# CPU.net
KiCad netlist of a schematic drawn in Altium Designer
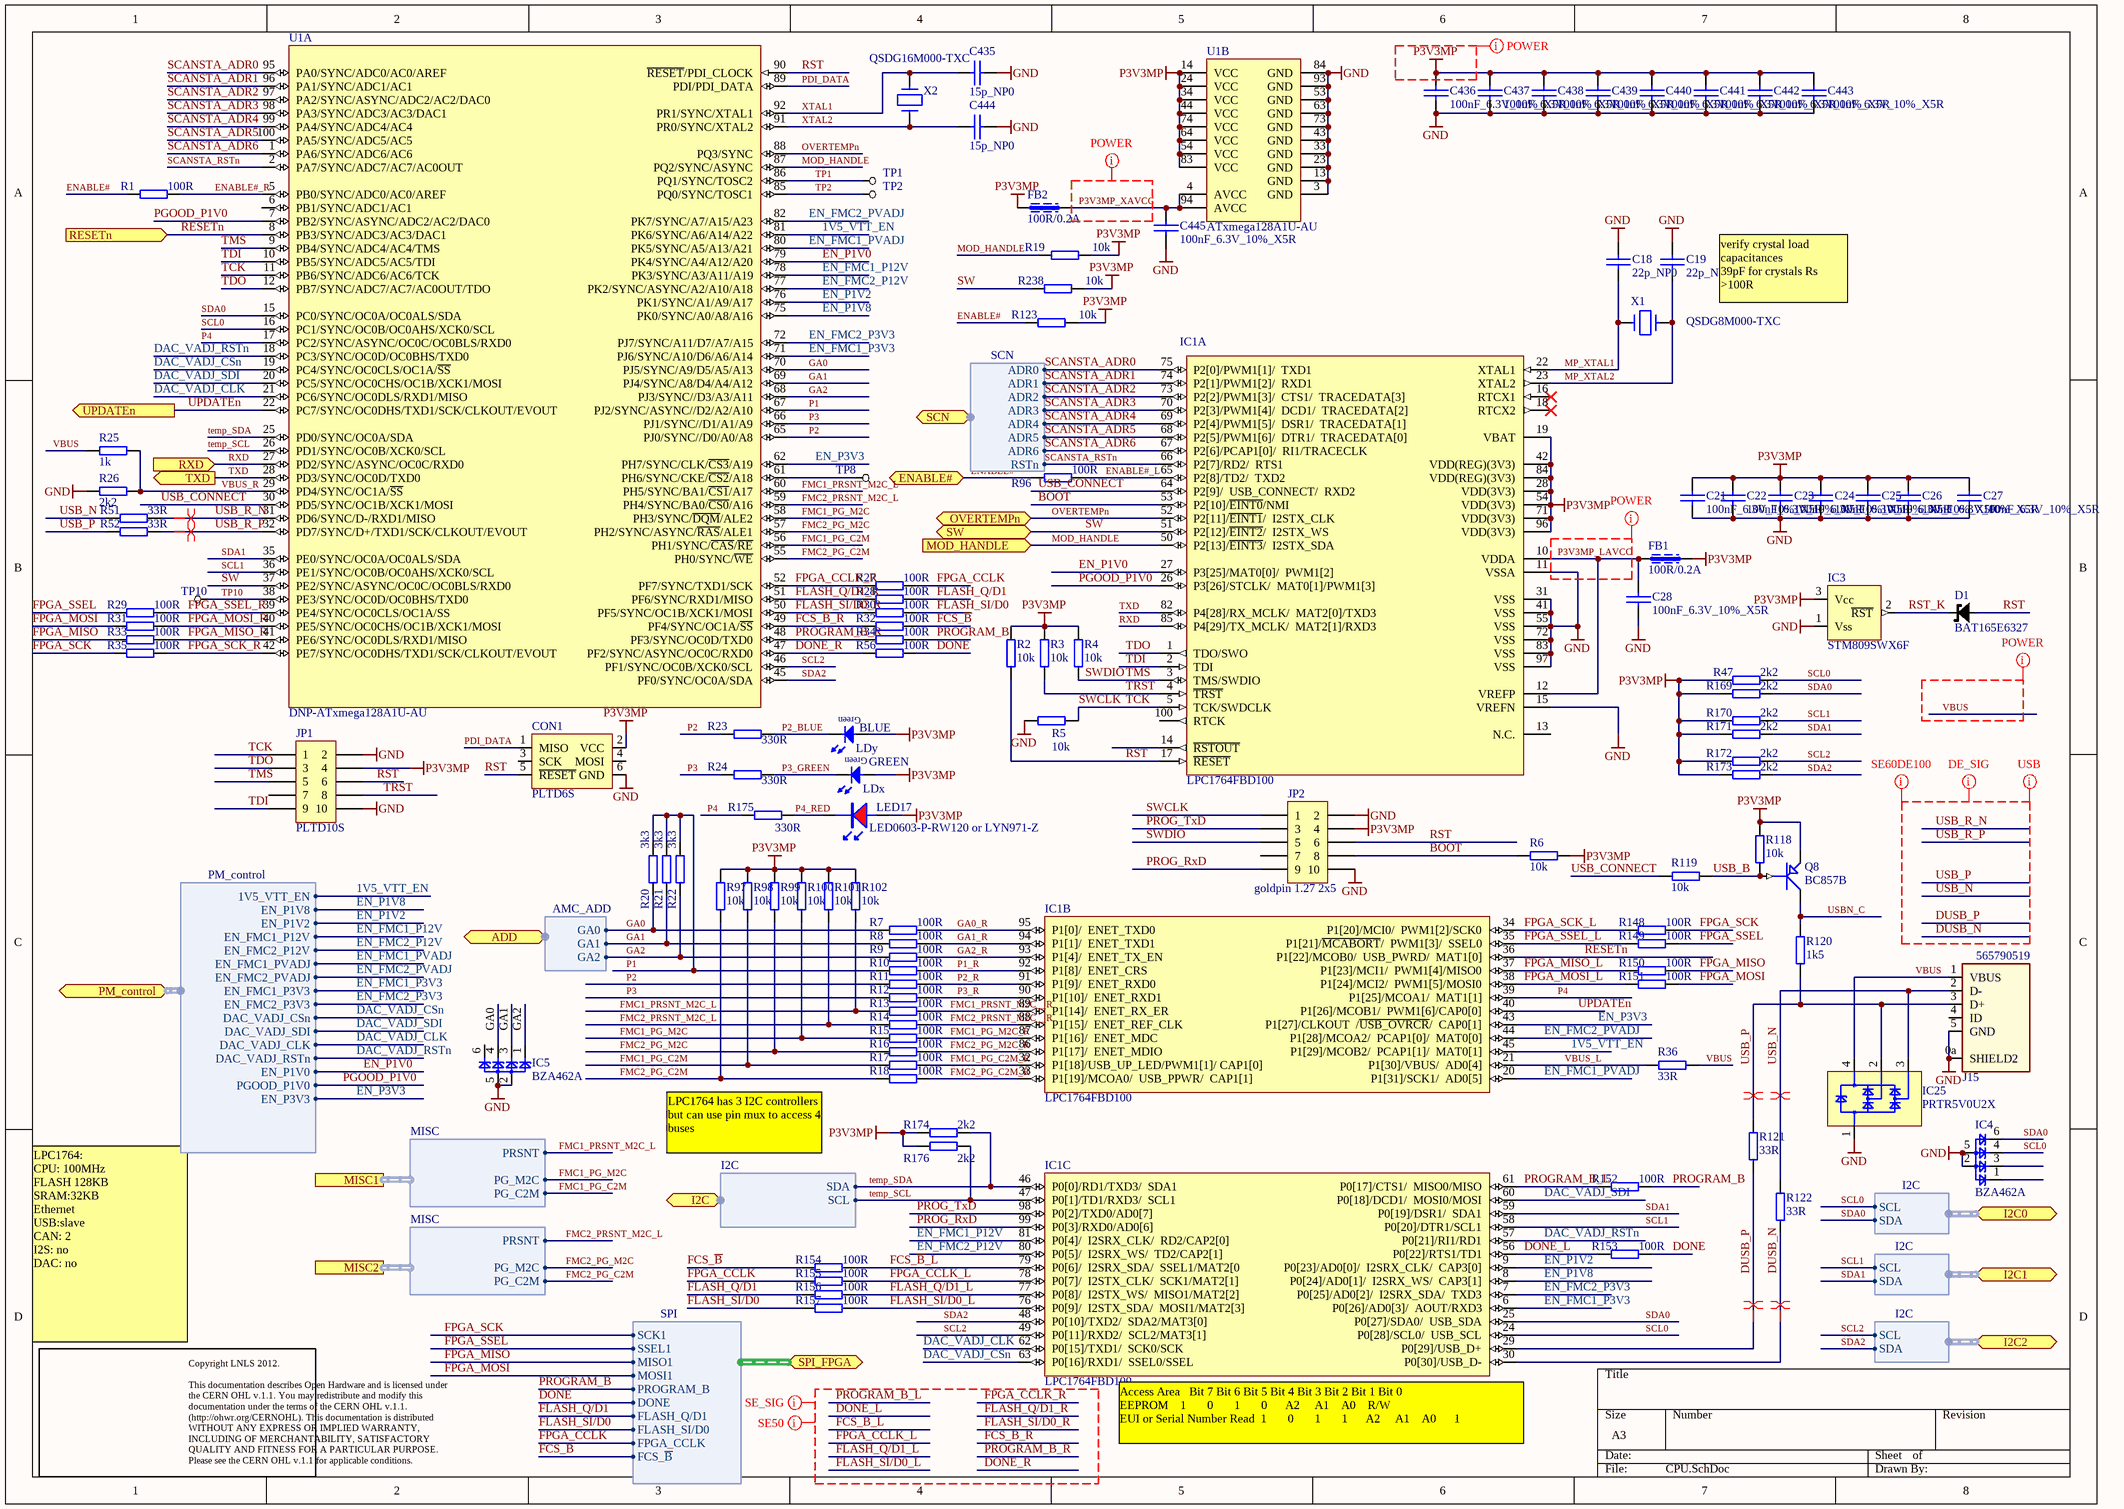
[diagram p0: CPU.SchDoc]

(export (version "E")
  (design (tool "Eeschema 10.0.6"))
  (components
    (comp (ref "C18")
      (value "22p_NP0")
      (footprint "0402C")
      (description "Capacitor SMD")
      (libsource (lib "LIBRARY_SCH") (part "CAP_SMD_0201"))
    )
    (comp (ref "C19")
      (value "22p_NP0")
      (footprint "0402C")
      (description "Capacitor SMD")
      (libsource (lib "LIBRARY_SCH") (part "CAP_SMD_0201"))
    )
    (comp (ref "C21")
      (value "100nF_6.3V_10%_X5R")
      (footprint "0201C")
      (description "Capacitor SMD")
      (libsource (lib "LIBRARY_SCH") (part "CAP_SMD_0201"))
    )
    (comp (ref "C22")
      (value "100nF_6.3V_10%_X5R")
      (footprint "0201C")
      (description "Capacitor SMD")
      (libsource (lib "LIBRARY_SCH") (part "CAP_SMD_0201"))
    )
    (comp (ref "C23")
      (value "100nF_6.3V_10%_X5R")
      (footprint "0201C")
      (description "Capacitor SMD")
      (libsource (lib "LIBRARY_SCH") (part "CAP_SMD_0201"))
    )
    (comp (ref "C24")
      (value "100nF_6.3V_10%_X5R")
      (footprint "0201C")
      (description "Capacitor SMD")
      (libsource (lib "LIBRARY_SCH") (part "CAP_SMD_0201"))
    )
    (comp (ref "C25")
      (value "100nF_6.3V_10%_X5R")
      (footprint "0201C")
      (description "Capacitor SMD")
      (libsource (lib "LIBRARY_SCH") (part "CAP_SMD_0201"))
    )
    (comp (ref "C26")
      (value "100nF_6.3V_10%_X5R")
      (footprint "0201C")
      (description "Capacitor SMD")
      (libsource (lib "LIBRARY_SCH") (part "CAP_SMD_0201"))
    )
    (comp (ref "C27")
      (value "100nF_6.3V_10%_X5R")
      (footprint "0201C")
      (description "Capacitor SMD")
      (libsource (lib "LIBRARY_SCH") (part "CAP_SMD_0201"))
    )
    (comp (ref "C28")
      (value "100nF_6.3V_10%_X5R")
      (footprint "0201C")
      (description "Capacitor SMD")
      (libsource (lib "LIBRARY_SCH") (part "CAP_SMD_0201"))
    )
    (comp (ref "C435")
      (value "15p_NP0")
      (footprint "0402C")
      (description "Capacitor SMD")
      (libsource (lib "LIBRARY_SCH") (part "CAP_SMD_0201"))
    )
    (comp (ref "C436")
      (value "100nF_6.3V_10%_X5R")
      (footprint "0201C")
      (description "Capacitor SMD")
      (libsource (lib "LIBRARY_SCH") (part "CAP_SMD_0201"))
    )
    (comp (ref "C437")
      (value "100nF_6.3V_10%_X5R")
      (footprint "0201C")
      (description "Capacitor SMD")
      (libsource (lib "LIBRARY_SCH") (part "CAP_SMD_0201"))
    )
    (comp (ref "C438")
      (value "100nF_6.3V_10%_X5R")
      (footprint "0201C")
      (description "Capacitor SMD")
      (libsource (lib "LIBRARY_SCH") (part "CAP_SMD_0201"))
    )
    (comp (ref "C439")
      (value "100nF_6.3V_10%_X5R")
      (footprint "0201C")
      (description "Capacitor SMD")
      (libsource (lib "LIBRARY_SCH") (part "CAP_SMD_0201"))
    )
    (comp (ref "C440")
      (value "100nF_6.3V_10%_X5R")
      (footprint "0201C")
      (description "Capacitor SMD")
      (libsource (lib "LIBRARY_SCH") (part "CAP_SMD_0201"))
    )
    (comp (ref "C441")
      (value "100nF_6.3V_10%_X5R")
      (footprint "0201C")
      (description "Capacitor SMD")
      (libsource (lib "LIBRARY_SCH") (part "CAP_SMD_0201"))
    )
    (comp (ref "C442")
      (value "100nF_6.3V_10%_X5R")
      (footprint "0201C")
      (description "Capacitor SMD")
      (libsource (lib "LIBRARY_SCH") (part "CAP_SMD_0201"))
    )
    (comp (ref "C443")
      (value "100nF_6.3V_10%_X5R")
      (footprint "0201C")
      (description "Capacitor SMD")
      (libsource (lib "LIBRARY_SCH") (part "CAP_SMD_0201"))
    )
    (comp (ref "C444")
      (value "15p_NP0")
      (footprint "0402C")
      (description "Capacitor SMD")
      (libsource (lib "LIBRARY_SCH") (part "CAP_SMD_0201"))
    )
    (comp (ref "C445")
      (value "100nF_6.3V_10%_X5R")
      (footprint "0201C")
      (description "Capacitor SMD")
      (libsource (lib "LIBRARY_SCH") (part "CAP_SMD_0201"))
    )
    (comp (ref "CON1")
      (value "PLTD6S")
      (footprint "PLTD6S")
      (description "6x 2.54mm SMT  dual row pin header")
      (libsource (lib "LIBRARY_SCH") (part "CON_ISP"))
    )
    (comp (ref "D1")
      (value "BAT165E6327")
      (footprint "SOD323")
      (description "500mA, 40V, Shottky Diode")
      (libsource (lib "LIBRARY_SCH") (part "D_BAT165"))
    )
    (comp (ref "FB1")
      (value "100R/0.2A")
      (footprint "0402L")
      (description "ferrite bead 100R@100MHz 0.2A")
      (libsource (lib "LIBRARY_SCH") (part "L_FERRITE_BEAD_0402"))
    )
    (comp (ref "FB2")
      (value "100R/0.2A")
      (footprint "0402L")
      (description "ferrite bead 100R@100MHz 0.2A")
      (libsource (lib "LIBRARY_SCH") (part "L_FERRITE_BEAD_0402"))
    )
    (comp (ref "IC1")
      (value "LPC1764FBD100")
      (footprint "LQFP100-LPC")
      (description "ARM Cortex-M3 procesor")
      (libsource (lib "LIBRARY_SCH") (part "UPC_LPC1764"))
    )
    (comp (ref "IC3")
      (value "STM809SWX6F")
      (footprint "SOT-23")
      (description "2.93V  Reset circuit")
      (libsource (lib "LIBRARY_SCH") (part "VMON_STM809"))
    )
    (comp (ref "IC4")
      (value "BZA462A")
      (footprint "SOT23-6")
      (description "Quadruple 4V ESD transient voltage suppressor")
      (libsource (lib "LIBRARY_SCH") (part "D_TVS_BZA462A"))
    )
    (comp (ref "IC5")
      (value "BZA462A")
      (footprint "SOT23-6")
      (description "Quadruple 4V ESD transient voltage suppressor")
      (libsource (lib "LIBRARY_SCH") (part "D_TVS_BZA462A"))
    )
    (comp (ref "IC25")
      (value "PRTR5V0U2X")
      (footprint "sot143b")
      (description "dual 5.5 ESD transient voltage suppressor")
      (libsource (lib "LIBRARY_SCH") (part "D_TVS_PRTR5V0U2X"))
    )
    (comp (ref "J15")
      (value "565790519")
      (footprint "CON_USB_565790519")
      (description "USB mini B connector (Molex)")
      (fields (field (name "PART NUMBER") "10133"))
      (libsource (lib "LIBRARY_SCH") (part "CON_USB_B_MINI_TH"))
    )
    (comp (ref "JP1")
      (value "PLTD10S")
      (footprint "PLTD10S")
      (description "Goldpin 2.54mm, male header")
      (libsource (lib "LIBRARY_SCH") (part "CON_2x5 2.54 male SMT"))
    )
    (comp (ref "JP2")
      (value "goldpin 1.27 2x5")
      (footprint "CON_2x5_MINI")
      (description "PBTD10S")
      (libsource (lib "sch") (part "CON_HEADER 5X2"))
    )
    (comp (ref "LDx")
      (value "GREEN")
      (footprint "LED_AVAGO_HSME-C120")
      (description "LED BLUE")
      (fields (field (name "AUTHOR") "CERN DEM JMW"))
      (libsource (lib "ICs And Semiconductors") (part "LED Green 1C 2A"))
    )
    (comp (ref "LDy")
      (value "BLUE")
      (footprint "LED_AVAGO_HSME-C120")
      (description "LED BLUE")
      (fields (field (name "AUTHOR") "CERN DEM JMW"))
      (libsource (lib "ICs And Semiconductors") (part "LED Green 1C 2A"))
    )
    (comp (ref "LED17")
      (value "LED0603-P-RW120 or LYN971-Z")
      (footprint "led_0603R")
      (description "LED 0603 red")
      (libsource (lib "LIBRARY_SCH") (part "LED_0603R"))
    )
    (comp (ref "Q8")
      (value "BC857B")
      (footprint "SOT-23")
      (description "Transistor")
      (libsource (lib "LIBRARY_SCH") (part "Q_BC857B"))
    )
    (comp (ref "R1")
      (value "100R")
      (footprint "0402R")
      (description "SMD Resistor")
      (libsource (lib "LIBRARY_SCH") (part "RES_0402"))
    )
    (comp (ref "R2")
      (value "10k")
      (footprint "0402R")
      (description "SMD Resistor")
      (libsource (lib "LIBRARY_SCH") (part "RES_0402"))
    )
    (comp (ref "R3")
      (value "10k")
      (footprint "0402R")
      (description "SMD Resistor")
      (libsource (lib "LIBRARY_SCH") (part "RES_0402"))
    )
    (comp (ref "R4")
      (value "10k")
      (footprint "0402R")
      (description "SMD Resistor")
      (libsource (lib "LIBRARY_SCH") (part "RES_0402"))
    )
    (comp (ref "R5")
      (value "10k")
      (footprint "0402R")
      (description "SMD Resistor")
      (libsource (lib "LIBRARY_SCH") (part "RES_0402"))
    )
    (comp (ref "R6")
      (value "10k")
      (footprint "0402R")
      (description "SMD Resistor")
      (libsource (lib "LIBRARY_SCH") (part "RES_0402"))
    )
    (comp (ref "R7")
      (value "100R")
      (footprint "0402R")
      (description "SMD Resistor")
      (libsource (lib "LIBRARY_SCH") (part "RES_0402"))
    )
    (comp (ref "R8")
      (value "100R")
      (footprint "0402R")
      (description "SMD Resistor")
      (libsource (lib "LIBRARY_SCH") (part "RES_0402"))
    )
    (comp (ref "R9")
      (value "100R")
      (footprint "0402R")
      (description "SMD Resistor")
      (libsource (lib "LIBRARY_SCH") (part "RES_0402"))
    )
    (comp (ref "R10")
      (value "100R")
      (footprint "0402R")
      (description "SMD Resistor")
      (libsource (lib "LIBRARY_SCH") (part "RES_0402"))
    )
    (comp (ref "R11")
      (value "100R")
      (footprint "0402R")
      (description "SMD Resistor")
      (libsource (lib "LIBRARY_SCH") (part "RES_0402"))
    )
    (comp (ref "R12")
      (value "100R")
      (footprint "0402R")
      (description "SMD Resistor")
      (libsource (lib "LIBRARY_SCH") (part "RES_0402"))
    )
    (comp (ref "R13")
      (value "100R")
      (footprint "0402R")
      (description "SMD Resistor")
      (libsource (lib "LIBRARY_SCH") (part "RES_0402"))
    )
    (comp (ref "R14")
      (value "100R")
      (footprint "0402R")
      (description "SMD Resistor")
      (libsource (lib "LIBRARY_SCH") (part "RES_0402"))
    )
    (comp (ref "R15")
      (value "100R")
      (footprint "0402R")
      (description "SMD Resistor")
      (libsource (lib "LIBRARY_SCH") (part "RES_0402"))
    )
    (comp (ref "R16")
      (value "100R")
      (footprint "0402R")
      (description "SMD Resistor")
      (libsource (lib "LIBRARY_SCH") (part "RES_0402"))
    )
    (comp (ref "R17")
      (value "100R")
      (footprint "0402R")
      (description "SMD Resistor")
      (libsource (lib "LIBRARY_SCH") (part "RES_0402"))
    )
    (comp (ref "R18")
      (value "100R")
      (footprint "0402R")
      (description "SMD Resistor")
      (libsource (lib "LIBRARY_SCH") (part "RES_0402"))
    )
    (comp (ref "R19")
      (value "10k")
      (footprint "0402R")
      (description "SMD Resistor")
      (libsource (lib "LIBRARY_SCH") (part "RES_0402"))
    )
    (comp (ref "R20")
      (value "3k3")
      (footprint "0402R")
      (description "SMD Resistor")
      (libsource (lib "LIBRARY_SCH") (part "RES_0402"))
    )
    (comp (ref "R21")
      (value "3k3")
      (footprint "0402R")
      (description "SMD Resistor")
      (libsource (lib "LIBRARY_SCH") (part "RES_0402"))
    )
    (comp (ref "R22")
      (value "3k3")
      (footprint "0402R")
      (description "SMD Resistor")
      (libsource (lib "LIBRARY_SCH") (part "RES_0402"))
    )
    (comp (ref "R23")
      (value "330R")
      (footprint "0402R")
      (description "SMD Resistor")
      (libsource (lib "LIBRARY_SCH") (part "RES_0402"))
    )
    (comp (ref "R24")
      (value "330R")
      (footprint "0402R")
      (description "SMD Resistor")
      (libsource (lib "LIBRARY_SCH") (part "RES_0402"))
    )
    (comp (ref "R25")
      (value "1k")
      (footprint "0402R")
      (description "SMD Resistor")
      (libsource (lib "LIBRARY_SCH") (part "RES_0402"))
    )
    (comp (ref "R26")
      (value "2k2")
      (footprint "0402R")
      (description "SMD Resistor")
      (libsource (lib "LIBRARY_SCH") (part "RES_0402"))
    )
    (comp (ref "R27")
      (value "100R")
      (footprint "0402R")
      (description "SMD Resistor")
      (libsource (lib "LIBRARY_SCH") (part "RES_0402"))
    )
    (comp (ref "R28")
      (value "100R")
      (footprint "0402R")
      (description "SMD Resistor")
      (libsource (lib "LIBRARY_SCH") (part "RES_0402"))
    )
    (comp (ref "R29")
      (value "100R")
      (footprint "0402R")
      (description "SMD Resistor")
      (libsource (lib "LIBRARY_SCH") (part "RES_0402"))
    )
    (comp (ref "R30")
      (value "100R")
      (footprint "0402R")
      (description "SMD Resistor")
      (libsource (lib "LIBRARY_SCH") (part "RES_0402"))
    )
    (comp (ref "R31")
      (value "100R")
      (footprint "0402R")
      (description "SMD Resistor")
      (libsource (lib "LIBRARY_SCH") (part "RES_0402"))
    )
    (comp (ref "R32")
      (value "100R")
      (footprint "0402R")
      (description "SMD Resistor")
      (libsource (lib "LIBRARY_SCH") (part "RES_0402"))
    )
    (comp (ref "R33")
      (value "100R")
      (footprint "0402R")
      (description "SMD Resistor")
      (libsource (lib "LIBRARY_SCH") (part "RES_0402"))
    )
    (comp (ref "R34")
      (value "100R")
      (footprint "0402R")
      (description "SMD Resistor")
      (libsource (lib "LIBRARY_SCH") (part "RES_0402"))
    )
    (comp (ref "R35")
      (value "100R")
      (footprint "0402R")
      (description "SMD Resistor")
      (libsource (lib "LIBRARY_SCH") (part "RES_0402"))
    )
    (comp (ref "R36")
      (value "33R")
      (footprint "0402R")
      (description "SMD Resistor")
      (libsource (lib "LIBRARY_SCH") (part "RES_0402"))
    )
    (comp (ref "R47")
      (value "2k2")
      (footprint "0402R")
      (description "SMD Resistor")
      (libsource (lib "LIBRARY_SCH") (part "RES_0402"))
    )
    (comp (ref "R51")
      (value "33R")
      (footprint "0402R")
      (description "SMD Resistor")
      (libsource (lib "LIBRARY_SCH") (part "RES_0402"))
    )
    (comp (ref "R52")
      (value "33R")
      (footprint "0402R")
      (description "SMD Resistor")
      (libsource (lib "LIBRARY_SCH") (part "RES_0402"))
    )
    (comp (ref "R56")
      (value "100R")
      (footprint "0402R")
      (description "SMD Resistor")
      (libsource (lib "LIBRARY_SCH") (part "RES_0402"))
    )
    (comp (ref "R96")
      (value "100R")
      (footprint "0402R")
      (description "SMD Resistor")
      (libsource (lib "LIBRARY_SCH") (part "RES_0402"))
    )
    (comp (ref "R97")
      (value "10k")
      (footprint "0402R")
      (description "SMD Resistor")
      (libsource (lib "LIBRARY_SCH") (part "RES_0402"))
    )
    (comp (ref "R98")
      (value "10k")
      (footprint "0402R")
      (description "SMD Resistor")
      (libsource (lib "LIBRARY_SCH") (part "RES_0402"))
    )
    (comp (ref "R99")
      (value "10k")
      (footprint "0402R")
      (description "SMD Resistor")
      (libsource (lib "LIBRARY_SCH") (part "RES_0402"))
    )
    (comp (ref "R100")
      (value "10k")
      (footprint "0402R")
      (description "SMD Resistor")
      (libsource (lib "LIBRARY_SCH") (part "RES_0402"))
    )
    (comp (ref "R101")
      (value "10k")
      (footprint "0402R")
      (description "SMD Resistor")
      (libsource (lib "LIBRARY_SCH") (part "RES_0402"))
    )
    (comp (ref "R102")
      (value "10k")
      (footprint "0402R")
      (description "SMD Resistor")
      (libsource (lib "LIBRARY_SCH") (part "RES_0402"))
    )
    (comp (ref "R118")
      (value "10k")
      (footprint "0402R")
      (description "SMD Resistor")
      (libsource (lib "LIBRARY_SCH") (part "RES_0402"))
    )
    (comp (ref "R119")
      (value "10k")
      (footprint "0402R")
      (description "SMD Resistor")
      (libsource (lib "LIBRARY_SCH") (part "RES_0402"))
    )
    (comp (ref "R120")
      (value "1k5")
      (footprint "0402R")
      (description "SMD Resistor")
      (libsource (lib "LIBRARY_SCH") (part "RES_0402"))
    )
    (comp (ref "R121")
      (value "33R")
      (footprint "0402R")
      (description "SMD Resistor")
      (libsource (lib "LIBRARY_SCH") (part "RES_0402"))
    )
    (comp (ref "R122")
      (value "33R")
      (footprint "0402R")
      (description "SMD Resistor")
      (libsource (lib "LIBRARY_SCH") (part "RES_0402"))
    )
    (comp (ref "R123")
      (value "10k")
      (footprint "0402R")
      (description "SMD Resistor")
      (libsource (lib "LIBRARY_SCH") (part "RES_0402"))
    )
    (comp (ref "R148")
      (value "100R")
      (footprint "0402R")
      (description "SMD Resistor")
      (libsource (lib "LIBRARY_SCH") (part "RES_0402"))
    )
    (comp (ref "R149")
      (value "100R")
      (footprint "0402R")
      (description "SMD Resistor")
      (libsource (lib "LIBRARY_SCH") (part "RES_0402"))
    )
    (comp (ref "R150")
      (value "100R")
      (footprint "0402R")
      (description "SMD Resistor")
      (libsource (lib "LIBRARY_SCH") (part "RES_0402"))
    )
    (comp (ref "R151")
      (value "100R")
      (footprint "0402R")
      (description "SMD Resistor")
      (libsource (lib "LIBRARY_SCH") (part "RES_0402"))
    )
    (comp (ref "R152")
      (value "100R")
      (footprint "0402R")
      (description "SMD Resistor")
      (libsource (lib "LIBRARY_SCH") (part "RES_0402"))
    )
    (comp (ref "R153")
      (value "100R")
      (footprint "0402R")
      (description "SMD Resistor")
      (libsource (lib "LIBRARY_SCH") (part "RES_0402"))
    )
    (comp (ref "R154")
      (value "100R")
      (footprint "0402R")
      (description "SMD Resistor")
      (libsource (lib "LIBRARY_SCH") (part "RES_0402"))
    )
    (comp (ref "R155")
      (value "100R")
      (footprint "0402R")
      (description "SMD Resistor")
      (libsource (lib "LIBRARY_SCH") (part "RES_0402"))
    )
    (comp (ref "R156")
      (value "100R")
      (footprint "0402R")
      (description "SMD Resistor")
      (libsource (lib "LIBRARY_SCH") (part "RES_0402"))
    )
    (comp (ref "R157")
      (value "100R")
      (footprint "0402R")
      (description "SMD Resistor")
      (libsource (lib "LIBRARY_SCH") (part "RES_0402"))
    )
    (comp (ref "R169")
      (value "2k2")
      (footprint "0402R")
      (description "SMD Resistor")
      (libsource (lib "LIBRARY_SCH") (part "RES_0402"))
    )
    (comp (ref "R170")
      (value "2k2")
      (footprint "0402R")
      (description "SMD Resistor")
      (libsource (lib "LIBRARY_SCH") (part "RES_0402"))
    )
    (comp (ref "R171")
      (value "2k2")
      (footprint "0402R")
      (description "SMD Resistor")
      (libsource (lib "LIBRARY_SCH") (part "RES_0402"))
    )
    (comp (ref "R172")
      (value "2k2")
      (footprint "0402R")
      (description "SMD Resistor")
      (libsource (lib "LIBRARY_SCH") (part "RES_0402"))
    )
    (comp (ref "R173")
      (value "2k2")
      (footprint "0402R")
      (description "SMD Resistor")
      (libsource (lib "LIBRARY_SCH") (part "RES_0402"))
    )
    (comp (ref "R174")
      (value "2k2")
      (footprint "0402R")
      (description "SMD Resistor")
      (libsource (lib "LIBRARY_SCH") (part "RES_0402"))
    )
    (comp (ref "R175")
      (value "330R")
      (footprint "0402R")
      (description "SMD Resistor")
      (libsource (lib "LIBRARY_SCH") (part "RES_0402"))
    )
    (comp (ref "R176")
      (value "2k2")
      (footprint "0402R")
      (description "SMD Resistor")
      (libsource (lib "LIBRARY_SCH") (part "RES_0402"))
    )
    (comp (ref "R238")
      (value "10k")
      (footprint "0402R")
      (description "SMD Resistor")
      (libsource (lib "LIBRARY_SCH") (part "RES_0402"))
    )
    (comp (ref "TP1")
      (value "TP")
      (footprint "TP")
      (description "Testpoint")
      (libsource (lib "LIBRARY_SCH") (part "TP"))
    )
    (comp (ref "TP2")
      (value "TP")
      (footprint "TP")
      (description "Testpoint")
      (libsource (lib "LIBRARY_SCH") (part "TP"))
    )
    (comp (ref "TP8")
      (value "TP")
      (footprint "TP")
      (description "Testpoint")
      (libsource (lib "LIBRARY_SCH") (part "TP"))
    )
    (comp (ref "TP10")
      (value "TP")
      (footprint "TP")
      (description "Testpoint")
      (libsource (lib "LIBRARY_SCH") (part "TP"))
    )
    (comp (ref "U1")
      (value "ATxmega128A1U-AU")
      (footprint "TQFP100")
      (fields (field (name "PUBLISHER") "Altium Limited"))
      (libsource (lib "LIBRARY_SCH") (part "UPC_ATxmega128A1-AU"))
    )
    (comp (ref "X1")
      (value "QSDG8M000-TXC")
      (footprint "XTAL_5.0*3.2")
      (description "miniature crystal oscillator (Maritex) QSDG8M000-TXC")
      (libsource (lib "LIBRARY_SCH") (part "X_CRYSTAL_SMD_5.0*3.2"))
    )
    (comp (ref "X2")
      (value "QSDG16M000-TXC")
      (footprint "XTAL_5.0*3.2")
      (description "miniature crystal oscillator (Maritex) QSDG8M000-TXC")
      (libsource (lib "LIBRARY_SCH") (part "X_CRYSTAL_SMD_5.0*3.2"))
    )
  )
  (nets
    (net (code "7") (name "/1V5_VTT_EN") (class "Default")
      (node (ref "IC1") (pin "45") (pinfunction "P1[29]/MCOB2/__PCAP1[1]/__MAT0[1]_45") (pintype "bidirectional"))
      (node (ref "U1") (pin "81") (pinfunction "PK6/SYNC/A6/A14/A22_81") (pintype "bidirectional"))
    )
    (net (code "8") (name "/BOOT") (class "Default")
      (node (ref "IC1") (pin "53") (pinfunction "P2[10]/~{EINT0}/NMI_53") (pintype "bidirectional"))
      (node (ref "JP2") (pin "8") (pinfunction "8_8") (pintype "passive"))
      (node (ref "R6") (pin "1") (pinfunction "1_1") (pintype "passive"))
    )
    (net (code "9") (name "/DAC_VADJ_CLK") (class "Default")
      (node (ref "IC1") (pin "62") (pinfunction "P0[15]/TXD1/__SCK0/SCK_62") (pintype "bidirectional"))
      (node (ref "U1") (pin "21") (pinfunction "PC6/SYNC/OC0DLS/RXD1/MISO_21") (pintype "bidirectional"))
    )
    (net (code "10") (name "/DAC_VADJ_CSn") (class "Default")
      (node (ref "IC1") (pin "63") (pinfunction "P0[16]/RXD1/__SSEL0/SSEL_63") (pintype "bidirectional"))
      (node (ref "U1") (pin "19") (pinfunction "PC4/SYNC/OC0CLS/OC1A/~{SS}_19") (pintype "bidirectional"))
    )
    (net (code "11") (name "/DAC_VADJ_RSTn") (class "Default")
      (node (ref "IC1") (pin "57") (pinfunction "P0[21]/RI1/RD1_57") (pintype "bidirectional"))
      (node (ref "U1") (pin "18") (pinfunction "PC3/SYNC/OC0D/OC0BHS/TXD0_18") (pintype "bidirectional"))
    )
    (net (code "12") (name "/DAC_VADJ_SDI") (class "Default")
      (node (ref "IC1") (pin "60") (pinfunction "P0[18]/DCD1/__MOSI0/MOSI_60") (pintype "bidirectional"))
      (node (ref "U1") (pin "20") (pinfunction "PC5/SYNC/OC0CHS/OC1B/XCK1/MOSI_20") (pintype "bidirectional"))
    )
    (net (code "13") (name "/DONE") (class "Default")
      (node (ref "R153") (pin "2") (pinfunction "2_2") (pintype "passive"))
      (node (ref "R56") (pin "2") (pinfunction "2_2") (pintype "passive"))
    )
    (net (code "14") (name "/DONE_L") (class "Default")
      (node (ref "IC1") (pin "56") (pinfunction "P0[22]/RTS1/TD1_56") (pintype "bidirectional"))
      (node (ref "R153") (pin "1") (pinfunction "1_1") (pintype "passive"))
    )
    (net (code "15") (name "/DONE_R") (class "Default")
      (node (ref "R56") (pin "1") (pinfunction "1_1") (pintype "passive"))
      (node (ref "U1") (pin "47") (pinfunction "PF2/SYNC/ASYNC/OC0C/RXD0_47") (pintype "bidirectional"))
    )
    (net (code "16") (name "/DUSB_N") (class "Default")
      (node (ref "IC1") (pin "30") (pinfunction "P0[30]/USB_D-_30") (pintype "bidirectional"))
      (node (ref "R122") (pin "1") (pinfunction "1_1") (pintype "passive"))
    )
    (net (code "17") (name "/DUSB_P") (class "Default")
      (node (ref "IC1") (pin "29") (pinfunction "P0[29]/USB_D+_29") (pintype "bidirectional"))
      (node (ref "R121") (pin "1") (pinfunction "1_1") (pintype "passive"))
    )
    (net (code "18") (name "/ENABLE#") (class "Default")
      (node (ref "R1") (pin "1") (pinfunction "1_1") (pintype "passive"))
      (node (ref "R123") (pin "1") (pinfunction "1_1") (pintype "passive"))
      (node (ref "R96") (pin "1") (pinfunction "1_1") (pintype "passive"))
    )
    (net (code "19") (name "/ENABLE#_L") (class "Default")
      (node (ref "IC1") (pin "65") (pinfunction "P2[8]/TD2/__TXD2_65") (pintype "bidirectional"))
      (node (ref "R96") (pin "2") (pinfunction "2_2") (pintype "passive"))
    )
    (net (code "20") (name "/ENABLE#_R") (class "Default")
      (node (ref "R1") (pin "2") (pinfunction "2_2") (pintype "passive"))
      (node (ref "U1") (pin "5") (pinfunction "PB0/SYNC/ADC0/AC0/AREF_5") (pintype "bidirectional"))
    )
    (net (code "21") (name "/EN_FMC1_P3V3") (class "Default")
      (node (ref "IC1") (pin "6") (pinfunction "P0[26]/AD0[3]/__AOUT/RXD3_6") (pintype "bidirectional"))
      (node (ref "U1") (pin "71") (pinfunction "PJ6/SYNC/A10/D6/A6/A14_71") (pintype "bidirectional"))
    )
    (net (code "22") (name "/EN_FMC1_P12V") (class "Default")
      (node (ref "IC1") (pin "81") (pinfunction "P0[4]/__I2SRX_CLK/__RD2/CAP2[0]_81") (pintype "bidirectional"))
      (node (ref "U1") (pin "78") (pinfunction "PK3/SYNC/A3/A11/A19_78") (pintype "bidirectional"))
    )
    (net (code "23") (name "/EN_FMC1_PVADJ") (class "Default")
      (node (ref "IC1") (pin "20") (pinfunction "P1[31]/SCK1/__AD0[5]_20") (pintype "bidirectional"))
      (node (ref "U1") (pin "80") (pinfunction "PK5/SYNC/A5/A13/A21_80") (pintype "bidirectional"))
    )
    (net (code "24") (name "/EN_FMC2_P3V3") (class "Default")
      (node (ref "IC1") (pin "7") (pinfunction "P0[25]/AD0[2]/__I2SRX_SDA/__TXD3_7") (pintype "bidirectional"))
      (node (ref "U1") (pin "72") (pinfunction "PJ7/SYNC/A11/D7/A7/A15_72") (pintype "bidirectional"))
    )
    (net (code "25") (name "/EN_FMC2_P12V") (class "Default")
      (node (ref "IC1") (pin "80") (pinfunction "P0[5]/__I2SRX_WS/__TD2/CAP2[1]_80") (pintype "bidirectional"))
      (node (ref "U1") (pin "77") (pinfunction "PK2/SYNC/ASYNC/A2/A10/A18_77") (pintype "bidirectional"))
    )
    (net (code "26") (name "/EN_FMC2_PVADJ") (class "Default")
      (node (ref "IC1") (pin "44") (pinfunction "P1[28]/MCOA2/__PCAP1[0]/__MAT0[0]_44") (pintype "bidirectional"))
      (node (ref "U1") (pin "82") (pinfunction "PK7/SYNC/A7/A15/A23_82") (pintype "bidirectional"))
    )
    (net (code "27") (name "/EN_P1V0") (class "Default")
      (node (ref "IC1") (pin "27") (pinfunction "P3[25]/MAT0[0]/__PWM1[2]_27") (pintype "bidirectional"))
      (node (ref "U1") (pin "79") (pinfunction "PK4/SYNC/A4/A12/A20_79") (pintype "bidirectional"))
    )
    (net (code "28") (name "/EN_P1V2") (class "Default")
      (node (ref "IC1") (pin "9") (pinfunction "P0[23]/AD0[0]/__I2SRX_CLK/__CAP3[0]_9") (pintype "bidirectional"))
      (node (ref "U1") (pin "76") (pinfunction "PK1/SYNC/A1/A9/A17_76") (pintype "bidirectional"))
    )
    (net (code "29") (name "/EN_P1V8") (class "Default")
      (node (ref "IC1") (pin "8") (pinfunction "P0[24]/AD0[1]/__I2SRX_WS/__CAP3[1]_8") (pintype "bidirectional"))
      (node (ref "U1") (pin "75") (pinfunction "PK0/SYNC/A0/A8/A16_75") (pintype "bidirectional"))
    )
    (net (code "30") (name "/EN_P3V3") (class "Default")
      (node (ref "IC1") (pin "43") (pinfunction "P1[27]/CLKOUT__/~{USB_OVRCR}/__CAP0[1]_43") (pintype "bidirectional"))
      (node (ref "U1") (pin "62") (pinfunction "PH7/SYNC/CLK/~{CS3}/A19_62") (pintype "bidirectional"))
    )
    (net (code "31") (name "/FCS_~{B}") (class "Default")
      (node (ref "R154") (pin "1") (pinfunction "1_1") (pintype "passive"))
      (node (ref "R32") (pin "2") (pinfunction "2_2") (pintype "passive"))
    )
    (net (code "32") (name "/FCS_~{B}_L") (class "Default")
      (node (ref "IC1") (pin "79") (pinfunction "P0[6]/__I2SRX_SDA/__SSEL1/MAT2[0_79") (pintype "bidirectional"))
      (node (ref "R154") (pin "2") (pinfunction "2_2") (pintype "passive"))
    )
    (net (code "33") (name "/FCS_~{B}_R") (class "Default")
      (node (ref "R32") (pin "1") (pinfunction "1_1") (pintype "passive"))
      (node (ref "U1") (pin "49") (pinfunction "PF4/SYNC/OC1A/~{SS}_49") (pintype "bidirectional"))
    )
    (net (code "34") (name "/FLASH_Q{slash}D1") (class "Default")
      (node (ref "R156") (pin "1") (pinfunction "1_1") (pintype "passive"))
      (node (ref "R28") (pin "2") (pinfunction "2_2") (pintype "passive"))
    )
    (net (code "35") (name "/FLASH_Q{slash}D1_L") (class "Default")
      (node (ref "IC1") (pin "77") (pinfunction "P0[8]/__I2STX_WS/__MISO1/MAT2[2]_77") (pintype "bidirectional"))
      (node (ref "R156") (pin "2") (pinfunction "2_2") (pintype "passive"))
    )
    (net (code "36") (name "/FLASH_Q{slash}D1_R") (class "Default")
      (node (ref "R28") (pin "1") (pinfunction "1_1") (pintype "passive"))
      (node (ref "U1") (pin "51") (pinfunction "PF6/SYNC/RXD1/MISO_51") (pintype "bidirectional"))
    )
    (net (code "37") (name "/FLASH_SI{slash}D0") (class "Default")
      (node (ref "R157") (pin "1") (pinfunction "1_1") (pintype "passive"))
      (node (ref "R30") (pin "2") (pinfunction "2_2") (pintype "passive"))
    )
    (net (code "38") (name "/FLASH_SI{slash}D0_L") (class "Default")
      (node (ref "IC1") (pin "76") (pinfunction "P0[9]/__I2STX_SDA/__MOSI1/MAT2[3]_76") (pintype "bidirectional"))
      (node (ref "R157") (pin "2") (pinfunction "2_2") (pintype "passive"))
    )
    (net (code "39") (name "/FLASH_SI{slash}D0_R") (class "Default")
      (node (ref "R30") (pin "1") (pinfunction "1_1") (pintype "passive"))
      (node (ref "U1") (pin "50") (pinfunction "PF5/SYNC/OC1B/XCK1/MOSI_50") (pintype "bidirectional"))
    )
    (net (code "40") (name "/FMC1_PG_C2M") (class "Default")
      (node (ref "R17") (pin "1") (pinfunction "1_1") (pintype "passive"))
      (node (ref "R98") (pin "1") (pinfunction "1_1") (pintype "passive"))
      (node (ref "U1") (pin "56") (pinfunction "PH1/SYNC/~{CAS}/~{RE}_56") (pintype "bidirectional"))
    )
    (net (code "41") (name "/FMC1_PG_C2M_R") (class "Default")
      (node (ref "IC1") (pin "32") (pinfunction "P1[18]/USB_UP_LED/PWM1[1]/_CAP1[0]_32") (pintype "bidirectional"))
      (node (ref "R17") (pin "2") (pinfunction "2_2") (pintype "passive"))
    )
    (net (code "42") (name "/FMC1_PG_M2C") (class "Default")
      (node (ref "R100") (pin "1") (pinfunction "1_1") (pintype "passive"))
      (node (ref "R15") (pin "1") (pinfunction "1_1") (pintype "passive"))
      (node (ref "U1") (pin "58") (pinfunction "PH3/SYNC/~{DQM}/ALE2_58") (pintype "bidirectional"))
    )
    (net (code "43") (name "/FMC1_PG_M2C_R") (class "Default")
      (node (ref "IC1") (pin "87") (pinfunction "P1[16]/__ENET_MDC_87") (pintype "bidirectional"))
      (node (ref "R15") (pin "2") (pinfunction "2_2") (pintype "passive"))
    )
    (net (code "44") (name "/FMC1_PRSNT_M2C_L") (class "Default")
      (node (ref "R102") (pin "1") (pinfunction "1_1") (pintype "passive"))
      (node (ref "R13") (pin "1") (pinfunction "1_1") (pintype "passive"))
      (node (ref "U1") (pin "60") (pinfunction "PH5/SYNC/BA1/~{CS1}/A17_60") (pintype "bidirectional"))
    )
    (net (code "45") (name "/FMC1_PRSNT_M2C__R") (class "Default")
      (node (ref "IC1") (pin "89") (pinfunction "P1[14]/__ENET_RX_ER_89") (pintype "bidirectional"))
      (node (ref "R13") (pin "2") (pinfunction "2_2") (pintype "passive"))
    )
    (net (code "46") (name "/FMC2_PG_C2M") (class "Default")
      (node (ref "R18") (pin "1") (pinfunction "1_1") (pintype "passive"))
      (node (ref "R97") (pin "1") (pinfunction "1_1") (pintype "passive"))
      (node (ref "U1") (pin "55") (pinfunction "PH0/SYNC/~{WE}_55") (pintype "bidirectional"))
    )
    (net (code "47") (name "/FMC2_PG_C2M_R") (class "Default")
      (node (ref "IC1") (pin "33") (pinfunction "P1[19]/MCOA0/__USB_PPWR/__CAP1[1]_33") (pintype "bidirectional"))
      (node (ref "R18") (pin "2") (pinfunction "2_2") (pintype "passive"))
    )
    (net (code "48") (name "/FMC2_PG_M2C") (class "Default")
      (node (ref "R16") (pin "1") (pinfunction "1_1") (pintype "passive"))
      (node (ref "R99") (pin "1") (pinfunction "1_1") (pintype "passive"))
      (node (ref "U1") (pin "57") (pinfunction "PH2/SYNC/ASYNC/~{RAS}/ALE1_57") (pintype "bidirectional"))
    )
    (net (code "49") (name "/FMC2_PG_M2C_R") (class "Default")
      (node (ref "IC1") (pin "86") (pinfunction "P1[17]/__ENET_MDIO_86") (pintype "bidirectional"))
      (node (ref "R16") (pin "2") (pinfunction "2_2") (pintype "passive"))
    )
    (net (code "50") (name "/FMC2_PRSNT_M2C_L") (class "Default")
      (node (ref "R101") (pin "1") (pinfunction "1_1") (pintype "passive"))
      (node (ref "R14") (pin "1") (pinfunction "1_1") (pintype "passive"))
      (node (ref "U1") (pin "59") (pinfunction "PH4/SYNC/BA0/~{CS0}/A16_59") (pintype "bidirectional"))
    )
    (net (code "51") (name "/FMC2_PRSNT_M2C__R") (class "Default")
      (node (ref "IC1") (pin "88") (pinfunction "P1[15]/__ENET_REF_CLK_88") (pintype "bidirectional"))
      (node (ref "R14") (pin "2") (pinfunction "2_2") (pintype "passive"))
    )
    (net (code "52") (name "/FPGA_CCLK") (class "Default")
      (node (ref "R155") (pin "1") (pinfunction "1_1") (pintype "passive"))
      (node (ref "R27") (pin "2") (pinfunction "2_2") (pintype "passive"))
    )
    (net (code "53") (name "/FPGA_CCLK_L") (class "Default")
      (node (ref "IC1") (pin "78") (pinfunction "P0[7]/__I2STX_CLK/__SCK1/MAT2[1]_78") (pintype "bidirectional"))
      (node (ref "R155") (pin "2") (pinfunction "2_2") (pintype "passive"))
    )
    (net (code "54") (name "/FPGA_CCLK_R") (class "Default")
      (node (ref "R27") (pin "1") (pinfunction "1_1") (pintype "passive"))
      (node (ref "U1") (pin "52") (pinfunction "PF7/SYNC/TXD1/SCK_52") (pintype "bidirectional"))
    )
    (net (code "55") (name "/FPGA_MISO") (class "Default")
      (node (ref "R150") (pin "2") (pinfunction "2_2") (pintype "passive"))
      (node (ref "R33") (pin "1") (pinfunction "1_1") (pintype "passive"))
    )
    (net (code "56") (name "/FPGA_MISO_L") (class "Default")
      (node (ref "IC1") (pin "37") (pinfunction "P1[23]/MCI1/__PWM1[4]/MISO0_37") (pintype "bidirectional"))
      (node (ref "R150") (pin "1") (pinfunction "1_1") (pintype "passive"))
    )
    (net (code "57") (name "/FPGA_MISO_R") (class "Default")
      (node (ref "R33") (pin "2") (pinfunction "2_2") (pintype "passive"))
      (node (ref "U1") (pin "41") (pinfunction "PE6/SYNC/OC0DLS/RXD1/MISO_41") (pintype "bidirectional"))
    )
    (net (code "58") (name "/FPGA_MOSI") (class "Default")
      (node (ref "R151") (pin "2") (pinfunction "2_2") (pintype "passive"))
      (node (ref "R31") (pin "1") (pinfunction "1_1") (pintype "passive"))
    )
    (net (code "59") (name "/FPGA_MOSI_L") (class "Default")
      (node (ref "IC1") (pin "38") (pinfunction "P1[24]/MCI2/__PWM1[5]/MOSI0_38") (pintype "bidirectional"))
      (node (ref "R151") (pin "1") (pinfunction "1_1") (pintype "passive"))
    )
    (net (code "60") (name "/FPGA_MOSI_R") (class "Default")
      (node (ref "R31") (pin "2") (pinfunction "2_2") (pintype "passive"))
      (node (ref "U1") (pin "40") (pinfunction "PE5/SYNC/OC0CHS/OC1B/XCK1/MOSI_40") (pintype "bidirectional"))
    )
    (net (code "61") (name "/FPGA_SCK") (class "Default")
      (node (ref "R148") (pin "2") (pinfunction "2_2") (pintype "passive"))
      (node (ref "R35") (pin "1") (pinfunction "1_1") (pintype "passive"))
    )
    (net (code "62") (name "/FPGA_SCK_L") (class "Default")
      (node (ref "IC1") (pin "34") (pinfunction "P1[20]/MCI0/__PWM1[2]/SCK0_34") (pintype "bidirectional"))
      (node (ref "R148") (pin "1") (pinfunction "1_1") (pintype "passive"))
    )
    (net (code "63") (name "/FPGA_SCK_R") (class "Default")
      (node (ref "R35") (pin "2") (pinfunction "2_2") (pintype "passive"))
      (node (ref "U1") (pin "42") (pinfunction "PE7/SYNC/OC0DHS/TXD1/SCK/CLKOUT/EVOUT_42") (pintype "bidirectional"))
    )
    (net (code "64") (name "/FPGA_SSEL") (class "Default")
      (node (ref "R149") (pin "2") (pinfunction "2_2") (pintype "passive"))
      (node (ref "R29") (pin "1") (pinfunction "1_1") (pintype "passive"))
    )
    (net (code "65") (name "/FPGA_SSEL_L") (class "Default")
      (node (ref "IC1") (pin "35") (pinfunction "P1[21]/~{MCABORT}/__PWM1[3]/__SSEL0_35") (pintype "bidirectional"))
      (node (ref "R149") (pin "1") (pinfunction "1_1") (pintype "passive"))
    )
    (net (code "66") (name "/FPGA_SSEL_R") (class "Default")
      (node (ref "R29") (pin "2") (pinfunction "2_2") (pintype "passive"))
      (node (ref "U1") (pin "39") (pinfunction "PE4/SYNC/OC0CLS/OC1A/SS_39") (pintype "bidirectional"))
    )
    (net (code "67") (name "/GA0") (class "Default")
      (node (ref "IC5") (pin "4") (pinfunction "4_4") (pintype "passive"))
      (node (ref "R20") (pin "1") (pinfunction "1_1") (pintype "passive"))
      (node (ref "R7") (pin "1") (pinfunction "1_1") (pintype "passive"))
      (node (ref "U1") (pin "70") (pinfunction "PJ5/SYNC/A9/D5/A5/A13_70") (pintype "bidirectional"))
    )
    (net (code "68") (name "/GA0_R") (class "Default")
      (node (ref "IC1") (pin "95") (pinfunction "P1[0]/__ENET_TXD0_95") (pintype "bidirectional"))
      (node (ref "R7") (pin "2") (pinfunction "2_2") (pintype "passive"))
    )
    (net (code "69") (name "/GA1") (class "Default")
      (node (ref "IC5") (pin "3") (pinfunction "3_3") (pintype "passive"))
      (node (ref "R21") (pin "1") (pinfunction "1_1") (pintype "passive"))
      (node (ref "R8") (pin "1") (pinfunction "1_1") (pintype "passive"))
      (node (ref "U1") (pin "69") (pinfunction "PJ4/SYNC/A8/D4/A4/A12_69") (pintype "bidirectional"))
    )
    (net (code "70") (name "/GA1_R") (class "Default")
      (node (ref "IC1") (pin "94") (pinfunction "P1[1]/__ENET_TXD1_94") (pintype "bidirectional"))
      (node (ref "R8") (pin "2") (pinfunction "2_2") (pintype "passive"))
    )
    (net (code "71") (name "/GA2") (class "Default")
      (node (ref "IC5") (pin "1") (pinfunction "1_1") (pintype "passive"))
      (node (ref "R22") (pin "1") (pinfunction "1_1") (pintype "passive"))
      (node (ref "R9") (pin "1") (pinfunction "1_1") (pintype "passive"))
      (node (ref "U1") (pin "68") (pinfunction "PJ3/SYNC//D3/A3/A11_68") (pintype "bidirectional"))
    )
    (net (code "72") (name "/GA2_R") (class "Default")
      (node (ref "IC1") (pin "93") (pinfunction "P1[4]/__ENET_TX_EN_93") (pintype "bidirectional"))
      (node (ref "R9") (pin "2") (pinfunction "2_2") (pintype "passive"))
    )
    (net (code "73") (name "/MOD_HANDLE") (class "Default")
      (node (ref "IC1") (pin "50") (pinfunction "P2[13]/~{EINT3}/__I2STX_SDA_50") (pintype "bidirectional"))
      (node (ref "R19") (pin "1") (pinfunction "1_1") (pintype "passive"))
      (node (ref "U1") (pin "87") (pinfunction "PQ2/SYNC/ASYNC_87") (pintype "bidirectional"))
    )
    (net (code "74") (name "/MP_XTAL1") (class "Default")
      (node (ref "C18") (pin "2") (pinfunction "2_2") (pintype "passive"))
      (node (ref "IC1") (pin "22") (pinfunction "XTAL1_22") (pintype "input"))
      (node (ref "X1") (pin "1") (pinfunction "1_1") (pintype "passive"))
    )
    (net (code "75") (name "/MP_XTAL2") (class "Default")
      (node (ref "C19") (pin "2") (pinfunction "2_2") (pintype "passive"))
      (node (ref "IC1") (pin "23") (pinfunction "XTAL2_23") (pintype "output"))
      (node (ref "X1") (pin "2") (pinfunction "2_2") (pintype "passive"))
    )
    (net (code "76") (name "/OVERTEMPn") (class "Default")
      (node (ref "IC1") (pin "52") (pinfunction "P2[11]/~{EINT1}/__I2STX_CLK_52") (pintype "bidirectional"))
      (node (ref "U1") (pin "88") (pinfunction "PQ3/SYNC_88") (pintype "bidirectional"))
    )
    (net (code "77") (name "/P1") (class "Default")
      (node (ref "R10") (pin "1") (pinfunction "1_1") (pintype "passive"))
      (node (ref "R20") (pin "2") (pinfunction "2_2") (pintype "passive"))
      (node (ref "R21") (pin "2") (pinfunction "2_2") (pintype "passive"))
      (node (ref "R22") (pin "2") (pinfunction "2_2") (pintype "passive"))
      (node (ref "U1") (pin "67") (pinfunction "PJ2/SYNC/ASYNC//D2/A2/A10_67") (pintype "bidirectional"))
    )
    (net (code "78") (name "/P1_R") (class "Default")
      (node (ref "IC1") (pin "92") (pinfunction "P1[8]/__ENET_CRS_92") (pintype "bidirectional"))
      (node (ref "R10") (pin "2") (pinfunction "2_2") (pintype "passive"))
    )
    (net (code "79") (name "/P2") (class "Default")
      (node (ref "R11") (pin "1") (pinfunction "1_1") (pintype "passive"))
      (node (ref "R23") (pin "1") (pinfunction "1_1") (pintype "passive"))
      (node (ref "U1") (pin "65") (pinfunction "PJ0/SYNC//D0/A0/A8_65") (pintype "bidirectional"))
    )
    (net (code "80") (name "/P2_BLUE") (class "Default")
      (node (ref "LDy") (pin "1") (pinfunction "C_1") (pintype "passive"))
      (node (ref "R23") (pin "2") (pinfunction "2_2") (pintype "passive"))
    )
    (net (code "81") (name "/P2_R") (class "Default")
      (node (ref "IC1") (pin "91") (pinfunction "P1[9]/__ENET_RXD0_91") (pintype "bidirectional"))
      (node (ref "R11") (pin "2") (pinfunction "2_2") (pintype "passive"))
    )
    (net (code "82") (name "/P3") (class "Default")
      (node (ref "R12") (pin "1") (pinfunction "1_1") (pintype "passive"))
      (node (ref "R24") (pin "1") (pinfunction "1_1") (pintype "passive"))
      (node (ref "U1") (pin "66") (pinfunction "PJ1/SYNC//D1/A1/A9_66") (pintype "bidirectional"))
    )
    (net (code "83") (name "/P3V3MP_LAVCC") (class "Default")
      (node (ref "C28") (pin "1") (pinfunction "1_1") (pintype "passive"))
      (node (ref "FB1") (pin "1") (pinfunction "1_1") (pintype "passive"))
      (node (ref "IC1") (pin "10") (pinfunction "VDDA_10") (pintype "power_in"))
      (node (ref "IC1") (pin "12") (pinfunction "VREFP_12") (pintype "power_in"))
    )
    (net (code "84") (name "/P3V3MP_XAVCC") (class "Default")
      (node (ref "C445") (pin "1") (pinfunction "1_1") (pintype "passive"))
      (node (ref "FB2") (pin "2") (pinfunction "2_2") (pintype "passive"))
      (node (ref "U1") (pin "4") (pinfunction "AVCC_4") (pintype "power_in"))
      (node (ref "U1") (pin "94") (pinfunction "AVCC_94") (pintype "power_in"))
    )
    (net (code "85") (name "/P3_GREEN") (class "Default")
      (node (ref "LDx") (pin "1") (pinfunction "C_1") (pintype "passive"))
      (node (ref "R24") (pin "2") (pinfunction "2_2") (pintype "passive"))
    )
    (net (code "86") (name "/P3_R") (class "Default")
      (node (ref "IC1") (pin "90") (pinfunction "P1[10]/__ENET_RXD1_90") (pintype "bidirectional"))
      (node (ref "R12") (pin "2") (pinfunction "2_2") (pintype "passive"))
    )
    (net (code "87") (name "/P4") (class "Default")
      (node (ref "IC1") (pin "39") (pinfunction "P1[25]/MCOA1/__MAT1[1]_39") (pintype "bidirectional"))
      (node (ref "R175") (pin "1") (pinfunction "1_1") (pintype "passive"))
      (node (ref "U1") (pin "17") (pinfunction "PC2/SYNC/ASYNC/OC0C/OC0BLS/RXD0_17") (pintype "bidirectional"))
    )
    (net (code "88") (name "/P4_RED") (class "Default")
      (node (ref "LED17") (pin "K") (pinfunction "K_K") (pintype "passive"))
      (node (ref "R175") (pin "2") (pinfunction "2_2") (pintype "passive"))
    )
    (net (code "89") (name "/PDI_DATA") (class "Default")
      (node (ref "CON1") (pin "1") (pinfunction "MISO_1") (pintype "passive"))
      (node (ref "U1") (pin "89") (pinfunction "PDI/PDI_DATA_89") (pintype "bidirectional"))
    )
    (net (code "90") (name "/PGOOD_P1V0") (class "Default")
      (node (ref "IC1") (pin "26") (pinfunction "P3[26]/STCLK/__MAT0[1]/PWM1[3]_26") (pintype "bidirectional"))
      (node (ref "U1") (pin "7") (pinfunction "PB2/SYNC/ASYNC/ADC2/AC2/DAC0_7") (pintype "bidirectional"))
    )
    (net (code "91") (name "/PROGRAM_B") (class "Default")
      (node (ref "R152") (pin "2") (pinfunction "2_2") (pintype "passive"))
      (node (ref "R34") (pin "2") (pinfunction "2_2") (pintype "passive"))
    )
    (net (code "92") (name "/PROGRAM_B_L") (class "Default")
      (node (ref "IC1") (pin "61") (pinfunction "P0[17]/CTS1/__MISO0/MISO_61") (pintype "bidirectional"))
      (node (ref "R152") (pin "1") (pinfunction "1_1") (pintype "passive"))
    )
    (net (code "93") (name "/PROGRAM_B_R") (class "Default")
      (node (ref "R34") (pin "1") (pinfunction "1_1") (pintype "passive"))
      (node (ref "U1") (pin "48") (pinfunction "PF3/SYNC/OC0D/TXD0_48") (pintype "bidirectional"))
    )
    (net (code "94") (name "/PROG_RxD") (class "Default")
      (node (ref "IC1") (pin "99") (pinfunction "P0[3]/RXD0/AD0[6]_99") (pintype "bidirectional"))
      (node (ref "JP2") (pin "9") (pinfunction "9_9") (pintype "passive"))
    )
    (net (code "95") (name "/PROG_TxD") (class "Default")
      (node (ref "IC1") (pin "98") (pinfunction "P0[2]/TXD0/AD0[7]_98") (pintype "bidirectional"))
      (node (ref "JP2") (pin "3") (pinfunction "3_3") (pintype "passive"))
    )
    (net (code "96") (name "/RESETn") (class "Default")
      (node (ref "IC1") (pin "36") (pinfunction "P1[22]/MCOB0/__USB_PWRD/__MAT1[0]_36") (pintype "bidirectional"))
      (node (ref "U1") (pin "8") (pinfunction "PB3/SYNC/ADC3/AC3/DAC1_8") (pintype "bidirectional"))
    )
    (net (code "97") (name "/RST") (class "Default")
      (node (ref "CON1") (pin "5") (pinfunction "~{RESET}_5") (pintype "passive"))
      (node (ref "D1") (pin "A") (pinfunction "A_A") (pintype "passive"))
      (node (ref "IC1") (pin "17") (pinfunction "~{RESET}_17") (pintype "input"))
      (node (ref "JP1") (pin "6") (pinfunction "6_6") (pintype "passive"))
      (node (ref "JP2") (pin "6") (pinfunction "6_6") (pintype "passive"))
      (node (ref "R2") (pin "1") (pinfunction "1_1") (pintype "passive"))
      (node (ref "U1") (pin "90") (pinfunction "~{RESET}/PDI_CLOCK_90") (pintype "input"))
    )
    (net (code "98") (name "/RST_K") (class "Default")
      (node (ref "D1") (pin "K") (pinfunction "K_K") (pintype "passive"))
      (node (ref "IC3") (pin "2") (pinfunction "~{RST}_2") (pintype "output"))
    )
    (net (code "99") (name "/RXD") (class "Default")
      (node (ref "IC1") (pin "85") (pinfunction "P4[29]/TX_MCLK/__MAT2[1]/RXD3_85") (pintype "bidirectional"))
      (node (ref "U1") (pin "27") (pinfunction "PD2/SYNC/ASYNC/OC0C/RXD0_27") (pintype "bidirectional"))
    )
    (net (code "100") (name "/SCANSTA_ADR0") (class "Default")
      (node (ref "IC1") (pin "75") (pinfunction "P2[0]/PWM1[1]/__TXD1_75") (pintype "bidirectional"))
      (node (ref "U1") (pin "95") (pinfunction "PA0/SYNC/ADC0/AC0/AREF_95") (pintype "bidirectional"))
    )
    (net (code "101") (name "/SCANSTA_ADR1") (class "Default")
      (node (ref "IC1") (pin "74") (pinfunction "P2[1]/PWM1[2]/__RXD1_74") (pintype "bidirectional"))
      (node (ref "U1") (pin "96") (pinfunction "PA1/SYNC/ADC1/AC1_96") (pintype "bidirectional"))
    )
    (net (code "102") (name "/SCANSTA_ADR2") (class "Default")
      (node (ref "IC1") (pin "73") (pinfunction "P2[2]/PWM1[3]/__CTS1/__TRACEDATA[3]_73") (pintype "bidirectional"))
      (node (ref "U1") (pin "97") (pinfunction "PA2/SYNC/ASYNC/ADC2/AC2/DAC0_97") (pintype "bidirectional"))
    )
    (net (code "103") (name "/SCANSTA_ADR3") (class "Default")
      (node (ref "IC1") (pin "70") (pinfunction "P2[3]/PWM1[4]/__DCD1/__TRACEDATA[2]_70") (pintype "bidirectional"))
      (node (ref "U1") (pin "98") (pinfunction "PA3/SYNC/ADC3/AC3/DAC1_98") (pintype "bidirectional"))
    )
    (net (code "104") (name "/SCANSTA_ADR4") (class "Default")
      (node (ref "IC1") (pin "69") (pinfunction "P2[4]/PWM1[5]/__DSR1/__TRACEDATA[1]_69") (pintype "bidirectional"))
      (node (ref "U1") (pin "99") (pinfunction "PA4/SYNC/ADC4/AC4_99") (pintype "bidirectional"))
    )
    (net (code "105") (name "/SCANSTA_ADR5") (class "Default")
      (node (ref "IC1") (pin "68") (pinfunction "P2[5]/PWM1[6]/__DTR1/__TRACEDATA[0]_68") (pintype "bidirectional"))
      (node (ref "U1") (pin "100") (pinfunction "PA5/SYNC/ADC5/AC5_100") (pintype "bidirectional"))
    )
    (net (code "106") (name "/SCANSTA_ADR6") (class "Default")
      (node (ref "IC1") (pin "67") (pinfunction "P2[6]/PCAP1[0]/__RI1/TRACECLK_67") (pintype "bidirectional"))
      (node (ref "U1") (pin "1") (pinfunction "PA6/SYNC/ADC6/AC6_1") (pintype "bidirectional"))
    )
    (net (code "107") (name "/SCANSTA_RSTn") (class "Default")
      (node (ref "IC1") (pin "66") (pinfunction "P2[7]/RD2/__RTS1_66") (pintype "bidirectional"))
      (node (ref "U1") (pin "2") (pinfunction "PA7/SYNC/ADC7/AC7/AC0OUT_2") (pintype "bidirectional"))
    )
    (net (code "108") (name "/SCL0") (class "Default")
      (node (ref "IC1") (pin "24") (pinfunction "P0[28]/SCL0/__USB_SCL_24") (pintype "bidirectional"))
      (node (ref "IC4") (pin "4") (pinfunction "4_4") (pintype "passive"))
      (node (ref "R47") (pin "2") (pinfunction "2_2") (pintype "passive"))
      (node (ref "U1") (pin "16") (pinfunction "PC1/SYNC/OC0B/OC0AHS/XCK0/SCL_16") (pintype "bidirectional"))
    )
    (net (code "109") (name "/SCL1") (class "Default")
      (node (ref "IC1") (pin "58") (pinfunction "P0[20]/DTR1/SCL1_58") (pintype "bidirectional"))
      (node (ref "R170") (pin "2") (pinfunction "2_2") (pintype "passive"))
      (node (ref "U1") (pin "36") (pinfunction "PE1/SYNC/OC0B/OC0AHS/XCK0/SCL_36") (pintype "bidirectional"))
    )
    (net (code "110") (name "/SCL2") (class "Default")
      (node (ref "IC1") (pin "49") (pinfunction "P0[11]/RXD2/__SCL2/MAT3[1]_49") (pintype "bidirectional"))
      (node (ref "R172") (pin "2") (pinfunction "2_2") (pintype "passive"))
      (node (ref "U1") (pin "46") (pinfunction "PF1/SYNC/OC0B/XCK0/SCL_46") (pintype "bidirectional"))
    )
    (net (code "111") (name "/SDA0") (class "Default")
      (node (ref "IC1") (pin "25") (pinfunction "P0[27]/SDA0/__USB_SDA_25") (pintype "bidirectional"))
      (node (ref "IC4") (pin "6") (pinfunction "6_6") (pintype "passive"))
      (node (ref "R169") (pin "2") (pinfunction "2_2") (pintype "passive"))
      (node (ref "U1") (pin "15") (pinfunction "PC0/SYNC/OC0A/OC0ALS/SDA_15") (pintype "bidirectional"))
    )
    (net (code "112") (name "/SDA1") (class "Default")
      (node (ref "IC1") (pin "59") (pinfunction "P0[19]/DSR1/__SDA1_59") (pintype "bidirectional"))
      (node (ref "R171") (pin "2") (pinfunction "2_2") (pintype "passive"))
      (node (ref "U1") (pin "35") (pinfunction "PE0/SYNC/OC0A/OC0ALS/SDA_35") (pintype "bidirectional"))
    )
    (net (code "113") (name "/SDA2") (class "Default")
      (node (ref "IC1") (pin "48") (pinfunction "P0[10]/TXD2/__SDA2/MAT3[0]_48") (pintype "bidirectional"))
      (node (ref "R173") (pin "2") (pinfunction "2_2") (pintype "passive"))
      (node (ref "U1") (pin "45") (pinfunction "PF0/SYNC/OC0A/SDA_45") (pintype "bidirectional"))
    )
    (net (code "114") (name "/SW") (class "Default")
      (node (ref "IC1") (pin "51") (pinfunction "P2[12]/~{EINT2}/__I2STX_WS_51") (pintype "bidirectional"))
      (node (ref "R238") (pin "1") (pinfunction "1_1") (pintype "passive"))
      (node (ref "U1") (pin "37") (pinfunction "PE2/SYNC/ASYNC/OC0C/OC0BLS/RXD0_37") (pintype "bidirectional"))
    )
    (net (code "115") (name "/SWCLK") (class "Default")
      (node (ref "IC1") (pin "5") (pinfunction "TCK/SWDCLK_5") (pintype "input"))
      (node (ref "JP1") (pin "1") (pinfunction "1_1") (pintype "passive"))
      (node (ref "JP2") (pin "1") (pinfunction "1_1") (pintype "passive"))
      (node (ref "R5") (pin "1") (pinfunction "1_1") (pintype "passive"))
      (node (ref "U1") (pin "11") (pinfunction "PB6/SYNC/ADC6/AC6/TCK_11") (pintype "bidirectional"))
    )
    (net (code "116") (name "/SWDIO") (class "Default")
      (node (ref "IC1") (pin "3") (pinfunction "TMS/SWDIO_3") (pintype "bidirectional"))
      (node (ref "JP1") (pin "5") (pinfunction "5_5") (pintype "passive"))
      (node (ref "JP2") (pin "5") (pinfunction "5_5") (pintype "passive"))
      (node (ref "R4") (pin "1") (pinfunction "1_1") (pintype "passive"))
      (node (ref "U1") (pin "9") (pinfunction "PB4/SYNC/ADC4/AC4/TMS_9") (pintype "bidirectional"))
    )
    (net (code "117") (name "/TDI") (class "Default")
      (node (ref "IC1") (pin "2") (pinfunction "TDI_2") (pintype "input"))
      (node (ref "JP1") (pin "9") (pinfunction "9_9") (pintype "passive"))
      (node (ref "U1") (pin "10") (pinfunction "PB5/SYNC/ADC5/AC5/TDI_10") (pintype "bidirectional"))
    )
    (net (code "118") (name "/TDO") (class "Default")
      (node (ref "IC1") (pin "1") (pinfunction "TDO/SWO_1") (pintype "output"))
      (node (ref "JP1") (pin "3") (pinfunction "3_3") (pintype "passive"))
      (node (ref "U1") (pin "12") (pinfunction "PB7/SYNC/ADC7/AC7/AC0OUT/TDO_12") (pintype "bidirectional"))
    )
    (net (code "119") (name "/TP1") (class "Default")
      (node (ref "TP1") (pin "1") (pintype "passive"))
      (node (ref "U1") (pin "86") (pinfunction "PQ1/SYNC/TOSC2_86") (pintype "bidirectional"))
    )
    (net (code "120") (name "/TP2") (class "Default")
      (node (ref "TP2") (pin "1") (pintype "passive"))
      (node (ref "U1") (pin "85") (pinfunction "PQ0/SYNC/TOSC1_85") (pintype "bidirectional"))
    )
    (net (code "121") (name "/TP10") (class "Default")
      (node (ref "TP10") (pin "1") (pintype "passive"))
      (node (ref "U1") (pin "38") (pinfunction "PE3/SYNC/OC0D/OC0BHS/TXD0_38") (pintype "bidirectional"))
    )
    (net (code "122") (name "/TRST") (class "Default")
      (node (ref "IC1") (pin "4") (pinfunction "~{TRST}_4") (pintype "input"))
      (node (ref "JP1") (pin "8") (pinfunction "8_8") (pintype "passive"))
      (node (ref "R3") (pin "1") (pinfunction "1_1") (pintype "passive"))
    )
    (net (code "123") (name "/TXD") (class "Default")
      (node (ref "IC1") (pin "82") (pinfunction "P4[28]/RX_MCLK/__MAT2[0]/TXD3_82") (pintype "bidirectional"))
      (node (ref "U1") (pin "28") (pinfunction "PD3/SYNC/OC0D/TXD0_28") (pintype "bidirectional"))
    )
    (net (code "124") (name "/UPDATEn") (class "Default")
      (node (ref "IC1") (pin "40") (pinfunction "P1[26]/MCOB1/__PWM1[6]/CAP0[0]_40") (pintype "bidirectional"))
      (node (ref "U1") (pin "22") (pinfunction "PC7/SYNC/OC0DHS/TXD1/SCK/CLKOUT/EVOUT_22") (pintype "bidirectional"))
    )
    (net (code "125") (name "/USBN_C") (class "Default")
      (node (ref "Q8") (pin "3") (pinfunction "C_3") (pintype "passive"))
      (node (ref "R120") (pin "2") (pinfunction "2_2") (pintype "passive"))
    )
    (net (code "126") (name "/USB_B") (class "Default")
      (node (ref "Q8") (pin "1") (pinfunction "B_1") (pintype "input"))
      (node (ref "R118") (pin "1") (pinfunction "1_1") (pintype "passive"))
      (node (ref "R119") (pin "2") (pinfunction "2_2") (pintype "passive"))
    )
    (net (code "127") (name "/USB_CONNECT") (class "Default")
      (node (ref "IC1") (pin "64") (pinfunction "P2[9]/__USB_CONNECT/__RXD2_64") (pintype "bidirectional"))
      (node (ref "R119") (pin "1") (pinfunction "1_1") (pintype "passive"))
      (node (ref "U1") (pin "30") (pinfunction "PD5/SYNC/OC1B/XCK1/MOSI_30") (pintype "bidirectional"))
    )
    (net (code "128") (name "/USB_N") (class "Default")
      (node (ref "IC25") (pin "3") (pinfunction "3_3") (pintype "passive"))
      (node (ref "J15") (pin "2") (pinfunction "D-_2") (pintype "passive"))
      (node (ref "R122") (pin "2") (pinfunction "2_2") (pintype "passive"))
      (node (ref "R51") (pin "1") (pinfunction "1_1") (pintype "passive"))
    )
    (net (code "129") (name "/USB_P") (class "Default")
      (node (ref "IC25") (pin "2") (pinfunction "2_2") (pintype "passive"))
      (node (ref "J15") (pin "3") (pinfunction "D+_3") (pintype "passive"))
      (node (ref "R120") (pin "1") (pinfunction "1_1") (pintype "passive"))
      (node (ref "R121") (pin "2") (pinfunction "2_2") (pintype "passive"))
      (node (ref "R52") (pin "1") (pinfunction "1_1") (pintype "passive"))
    )
    (net (code "130") (name "/USB_R_N") (class "Default")
      (node (ref "R51") (pin "2") (pinfunction "2_2") (pintype "passive"))
      (node (ref "U1") (pin "31") (pinfunction "PD6/SYNC/D-/RXD1/MISO_31") (pintype "bidirectional"))
    )
    (net (code "131") (name "/USB_R_P") (class "Default")
      (node (ref "R52") (pin "2") (pinfunction "2_2") (pintype "passive"))
      (node (ref "U1") (pin "32") (pinfunction "PD7/SYNC/D+/TXD1/SCK/CLKOUT/EVOUT_32") (pintype "bidirectional"))
    )
    (net (code "132") (name "/VBUS") (class "Default")
      (node (ref "IC25") (pin "4") (pinfunction "4_4") (pintype "passive"))
      (node (ref "J15") (pin "1") (pinfunction "VBUS_1") (pintype "passive"))
      (node (ref "R25") (pin "2") (pinfunction "2_2") (pintype "passive"))
      (node (ref "R36") (pin "1") (pinfunction "1_1") (pintype "passive"))
    )
    (net (code "133") (name "/VBUS_L") (class "Default")
      (node (ref "IC1") (pin "21") (pinfunction "P1[30]/VBUS/__AD0[4]_21") (pintype "bidirectional"))
      (node (ref "R36") (pin "2") (pinfunction "2_2") (pintype "passive"))
    )
    (net (code "134") (name "/VBUS_R") (class "Default")
      (node (ref "R25") (pin "1") (pinfunction "1_1") (pintype "passive"))
      (node (ref "R26") (pin "1") (pinfunction "1_1") (pintype "passive"))
      (node (ref "U1") (pin "29") (pinfunction "PD4/SYNC/OC1A/~{SS}_29") (pintype "bidirectional"))
    )
    (net (code "135") (name "/XTAL1") (class "Default")
      (node (ref "C435") (pin "2") (pinfunction "2_2") (pintype "passive"))
      (node (ref "U1") (pin "92") (pinfunction "PR1/SYNC/XTAL1_92") (pintype "bidirectional"))
      (node (ref "X2") (pin "1") (pinfunction "1_1") (pintype "passive"))
    )
    (net (code "136") (name "/XTAL2") (class "Default")
      (node (ref "C444") (pin "2") (pinfunction "2_2") (pintype "passive"))
      (node (ref "U1") (pin "91") (pinfunction "PR0/SYNC/XTAL2_91") (pintype "bidirectional"))
      (node (ref "X2") (pin "2") (pinfunction "2_2") (pintype "passive"))
    )
    (net (code "137") (name "/temp_SCL") (class "Default")
      (node (ref "IC1") (pin "47") (pinfunction "P0[1]/TD1/RXD3/__SCL1_47") (pintype "bidirectional"))
      (node (ref "R176") (pin "2") (pinfunction "2_2") (pintype "passive"))
      (node (ref "U1") (pin "26") (pinfunction "PD1/SYNC/OC0B/XCK0/SCL_26") (pintype "bidirectional"))
    )
    (net (code "138") (name "/temp_SDA") (class "Default")
      (node (ref "IC1") (pin "46") (pinfunction "P0[0]/RD1/TXD3/__SDA1_46") (pintype "bidirectional"))
      (node (ref "R174") (pin "2") (pinfunction "2_2") (pintype "passive"))
      (node (ref "U1") (pin "25") (pinfunction "PD0/SYNC/OC0A/SDA_25") (pintype "bidirectional"))
    )
    (net (code "145") (name "GND") (class "Default")
      (node (ref "C18") (pin "1") (pinfunction "1_1") (pintype "passive"))
      (node (ref "C19") (pin "1") (pinfunction "1_1") (pintype "passive"))
      (node (ref "C21") (pin "1") (pinfunction "1_1") (pintype "passive"))
      (node (ref "C22") (pin "1") (pinfunction "1_1") (pintype "passive"))
      (node (ref "C23") (pin "1") (pinfunction "1_1") (pintype "passive"))
      (node (ref "C24") (pin "1") (pinfunction "1_1") (pintype "passive"))
      (node (ref "C25") (pin "1") (pinfunction "1_1") (pintype "passive"))
      (node (ref "C26") (pin "1") (pinfunction "1_1") (pintype "passive"))
      (node (ref "C27") (pin "1") (pinfunction "1_1") (pintype "passive"))
      (node (ref "C28") (pin "2") (pinfunction "2_2") (pintype "passive"))
      (node (ref "C435") (pin "1") (pinfunction "1_1") (pintype "passive"))
      (node (ref "C436") (pin "1") (pinfunction "1_1") (pintype "passive"))
      (node (ref "C437") (pin "1") (pinfunction "1_1") (pintype "passive"))
      (node (ref "C438") (pin "1") (pinfunction "1_1") (pintype "passive"))
      (node (ref "C439") (pin "1") (pinfunction "1_1") (pintype "passive"))
      (node (ref "C440") (pin "1") (pinfunction "1_1") (pintype "passive"))
      (node (ref "C441") (pin "1") (pinfunction "1_1") (pintype "passive"))
      (node (ref "C442") (pin "1") (pinfunction "1_1") (pintype "passive"))
      (node (ref "C443") (pin "1") (pinfunction "1_1") (pintype "passive"))
      (node (ref "C444") (pin "1") (pinfunction "1_1") (pintype "passive"))
      (node (ref "C445") (pin "2") (pinfunction "2_2") (pintype "passive"))
      (node (ref "CON1") (pin "6") (pinfunction "GND_6") (pintype "passive"))
      (node (ref "IC1") (pin "11") (pinfunction "VSSA_11") (pintype "power_in"))
      (node (ref "IC1") (pin "15") (pinfunction "VREFN_15") (pintype "power_in"))
      (node (ref "IC1") (pin "31") (pinfunction "VSS_31") (pintype "power_in"))
      (node (ref "IC1") (pin "41") (pinfunction "VSS_41") (pintype "power_in"))
      (node (ref "IC1") (pin "55") (pinfunction "VSS_55") (pintype "power_in"))
      (node (ref "IC1") (pin "72") (pinfunction "VSS_72") (pintype "power_in"))
      (node (ref "IC1") (pin "83") (pinfunction "VSS_83") (pintype "power_in"))
      (node (ref "IC1") (pin "97") (pinfunction "VSS_97") (pintype "power_in"))
      (node (ref "IC25") (pin "1") (pinfunction "1_1") (pintype "passive"))
      (node (ref "IC3") (pin "1") (pinfunction "Vss_1") (pintype "power_in"))
      (node (ref "IC4") (pin "2") (pinfunction "2_2") (pintype "passive"))
      (node (ref "IC4") (pin "5") (pinfunction "5_5") (pintype "passive"))
      (node (ref "IC5") (pin "2") (pinfunction "2_2") (pintype "passive"))
      (node (ref "IC5") (pin "5") (pinfunction "5_5") (pintype "passive"))
      (node (ref "J15") (pin "0") (pinfunction "SHIELD2_0") (pintype "passive"))
      (node (ref "J15") (pin "0a") (pinfunction "SHIELD2_0a") (pintype "passive"))
      (node (ref "J15") (pin "5") (pinfunction "GND_5") (pintype "passive"))
      (node (ref "JP1") (pin "10") (pinfunction "10_10") (pintype "passive"))
      (node (ref "JP1") (pin "2") (pinfunction "2_2") (pintype "passive"))
      (node (ref "JP2") (pin "10") (pinfunction "10_10") (pintype "passive"))
      (node (ref "JP2") (pin "2") (pinfunction "2_2") (pintype "passive"))
      (node (ref "R26") (pin "2") (pinfunction "2_2") (pintype "passive"))
      (node (ref "R5") (pin "2") (pinfunction "2_2") (pintype "passive"))
      (node (ref "U1") (pin "13") (pinfunction "GND_13") (pintype "power_in"))
      (node (ref "U1") (pin "23") (pinfunction "GND_23") (pintype "power_in"))
      (node (ref "U1") (pin "3") (pinfunction "GND_3") (pintype "power_in"))
      (node (ref "U1") (pin "33") (pinfunction "GND_33") (pintype "power_in"))
      (node (ref "U1") (pin "43") (pinfunction "GND_43") (pintype "power_in"))
      (node (ref "U1") (pin "53") (pinfunction "GND_53") (pintype "power_in"))
      (node (ref "U1") (pin "63") (pinfunction "GND_63") (pintype "power_in"))
      (node (ref "U1") (pin "73") (pinfunction "GND_73") (pintype "power_in"))
      (node (ref "U1") (pin "84") (pinfunction "GND_84") (pintype "power_in"))
      (node (ref "U1") (pin "93") (pinfunction "GND_93") (pintype "power_in"))
    )
    (net (code "146") (name "Net-(U1A-PH6{slash}SYNC{slash}CKE{slash}~{CS2}{slash}A18)") (class "Default")
      (node (ref "TP8") (pin "1") (pintype "passive"))
      (node (ref "U1") (pin "61") (pinfunction "PH6/SYNC/CKE/~{CS2}/A18_61") (pintype "bidirectional"))
    )
    (net (code "147") (name "P3V3MP") (class "Default")
      (node (ref "C21") (pin "2") (pinfunction "2_2") (pintype "passive"))
      (node (ref "C22") (pin "2") (pinfunction "2_2") (pintype "passive"))
      (node (ref "C23") (pin "2") (pinfunction "2_2") (pintype "passive"))
      (node (ref "C24") (pin "2") (pinfunction "2_2") (pintype "passive"))
      (node (ref "C25") (pin "2") (pinfunction "2_2") (pintype "passive"))
      (node (ref "C26") (pin "2") (pinfunction "2_2") (pintype "passive"))
      (node (ref "C27") (pin "2") (pinfunction "2_2") (pintype "passive"))
      (node (ref "C436") (pin "2") (pinfunction "2_2") (pintype "passive"))
      (node (ref "C437") (pin "2") (pinfunction "2_2") (pintype "passive"))
      (node (ref "C438") (pin "2") (pinfunction "2_2") (pintype "passive"))
      (node (ref "C439") (pin "2") (pinfunction "2_2") (pintype "passive"))
      (node (ref "C440") (pin "2") (pinfunction "2_2") (pintype "passive"))
      (node (ref "C441") (pin "2") (pinfunction "2_2") (pintype "passive"))
      (node (ref "C442") (pin "2") (pinfunction "2_2") (pintype "passive"))
      (node (ref "C443") (pin "2") (pinfunction "2_2") (pintype "passive"))
      (node (ref "CON1") (pin "2") (pinfunction "VCC_2") (pintype "passive"))
      (node (ref "FB1") (pin "2") (pinfunction "2_2") (pintype "passive"))
      (node (ref "FB2") (pin "1") (pinfunction "1_1") (pintype "passive"))
      (node (ref "IC1") (pin "19") (pinfunction "VBAT_19") (pintype "power_in"))
      (node (ref "IC1") (pin "28") (pinfunction "VDD(3V3)_28") (pintype "power_in"))
      (node (ref "IC1") (pin "42") (pinfunction "VDD(REG)(3V3)_42") (pintype "power_in"))
      (node (ref "IC1") (pin "54") (pinfunction "VDD(3V3)_54") (pintype "power_in"))
      (node (ref "IC1") (pin "71") (pinfunction "VDD(3V3)_71") (pintype "power_in"))
      (node (ref "IC1") (pin "84") (pinfunction "VDD(REG)(3V3)_84") (pintype "power_in"))
      (node (ref "IC1") (pin "96") (pinfunction "VDD(3V3)_96") (pintype "power_in"))
      (node (ref "IC3") (pin "3") (pinfunction "Vcc_3") (pintype "power_in"))
      (node (ref "JP1") (pin "4") (pinfunction "4_4") (pintype "passive"))
      (node (ref "JP2") (pin "4") (pinfunction "4_4") (pintype "passive"))
      (node (ref "LDx") (pin "2") (pinfunction "A_2") (pintype "passive"))
      (node (ref "LDy") (pin "2") (pinfunction "A_2") (pintype "passive"))
      (node (ref "LED17") (pin "A") (pinfunction "A_A") (pintype "passive"))
      (node (ref "Q8") (pin "2") (pinfunction "E_2") (pintype "passive"))
      (node (ref "R100") (pin "2") (pinfunction "2_2") (pintype "passive"))
      (node (ref "R101") (pin "2") (pinfunction "2_2") (pintype "passive"))
      (node (ref "R102") (pin "2") (pinfunction "2_2") (pintype "passive"))
      (node (ref "R118") (pin "2") (pinfunction "2_2") (pintype "passive"))
      (node (ref "R123") (pin "2") (pinfunction "2_2") (pintype "passive"))
      (node (ref "R169") (pin "1") (pinfunction "1_1") (pintype "passive"))
      (node (ref "R170") (pin "1") (pinfunction "1_1") (pintype "passive"))
      (node (ref "R171") (pin "1") (pinfunction "1_1") (pintype "passive"))
      (node (ref "R172") (pin "1") (pinfunction "1_1") (pintype "passive"))
      (node (ref "R173") (pin "1") (pinfunction "1_1") (pintype "passive"))
      (node (ref "R174") (pin "1") (pinfunction "1_1") (pintype "passive"))
      (node (ref "R176") (pin "1") (pinfunction "1_1") (pintype "passive"))
      (node (ref "R19") (pin "2") (pinfunction "2_2") (pintype "passive"))
      (node (ref "R2") (pin "2") (pinfunction "2_2") (pintype "passive"))
      (node (ref "R238") (pin "2") (pinfunction "2_2") (pintype "passive"))
      (node (ref "R3") (pin "2") (pinfunction "2_2") (pintype "passive"))
      (node (ref "R4") (pin "2") (pinfunction "2_2") (pintype "passive"))
      (node (ref "R47") (pin "1") (pinfunction "1_1") (pintype "passive"))
      (node (ref "R6") (pin "2") (pinfunction "2_2") (pintype "passive"))
      (node (ref "R97") (pin "2") (pinfunction "2_2") (pintype "passive"))
      (node (ref "R98") (pin "2") (pinfunction "2_2") (pintype "passive"))
      (node (ref "R99") (pin "2") (pinfunction "2_2") (pintype "passive"))
      (node (ref "U1") (pin "14") (pinfunction "VCC_14") (pintype "power_in"))
      (node (ref "U1") (pin "24") (pinfunction "VCC_24") (pintype "power_in"))
      (node (ref "U1") (pin "34") (pinfunction "VCC_34") (pintype "power_in"))
      (node (ref "U1") (pin "44") (pinfunction "VCC_44") (pintype "power_in"))
      (node (ref "U1") (pin "54") (pinfunction "VCC_54") (pintype "power_in"))
      (node (ref "U1") (pin "64") (pinfunction "VCC_64") (pintype "power_in"))
      (node (ref "U1") (pin "74") (pinfunction "VCC_74") (pintype "power_in"))
      (node (ref "U1") (pin "83") (pinfunction "VCC_83") (pintype "power_in"))
    )
    (net (code "148") (name "unconnected-(CON1-MOSI-Pad4)") (class "Default")
      (node (ref "CON1") (pin "4") (pinfunction "MOSI_4") (pintype "passive"))
    )
    (net (code "149") (name "unconnected-(CON1-SCK-Pad3)") (class "Default")
      (node (ref "CON1") (pin "3") (pinfunction "SCK_3") (pintype "passive"))
    )
    (net (code "150") (name "unconnected-(IC1A-N.C.-Pad13)") (class "Default")
      (node (ref "IC1") (pin "13") (pinfunction "N.C._13") (pintype "tri_state"))
    )
    (net (code "151") (name "unconnected-(IC1A-RTCK-Pad100)") (class "Default")
      (node (ref "IC1") (pin "100") (pinfunction "RTCK_100") (pintype "output"))
    )
    (net (code "152") (name "unconnected-(IC1A-RTCX1-Pad16)") (class "Default")
      (node (ref "IC1") (pin "16") (pinfunction "RTCX1_16") (pintype "input+no_connect"))
    )
    (net (code "153") (name "unconnected-(IC1A-RTCX2-Pad18)") (class "Default")
      (node (ref "IC1") (pin "18") (pinfunction "RTCX2_18") (pintype "output+no_connect"))
    )
    (net (code "154") (name "unconnected-(IC1A-~{RSTOUT}-Pad14)") (class "Default")
      (node (ref "IC1") (pin "14") (pinfunction "~{RSTOUT}_14") (pintype "output"))
    )
    (net (code "155") (name "unconnected-(IC4-Pad1)") (class "Default")
      (node (ref "IC4") (pin "1") (pinfunction "1_1") (pintype "passive"))
    )
    (net (code "156") (name "unconnected-(IC4-Pad3)") (class "Default")
      (node (ref "IC4") (pin "3") (pinfunction "3_3") (pintype "passive"))
    )
    (net (code "157") (name "unconnected-(IC5-Pad6)") (class "Default")
      (node (ref "IC5") (pin "6") (pinfunction "6_6") (pintype "passive"))
    )
    (net (code "158") (name "unconnected-(J15-ID-Pad4)") (class "Default")
      (node (ref "J15") (pin "4") (pinfunction "ID_4") (pintype "passive"))
    )
    (net (code "159") (name "unconnected-(JP1-Pad7)") (class "Default")
      (node (ref "JP1") (pin "7") (pinfunction "7_7") (pintype "passive"))
    )
    (net (code "160") (name "unconnected-(JP2-Pad7)") (class "Default")
      (node (ref "JP2") (pin "7") (pinfunction "7_7") (pintype "passive"))
    )
    (net (code "161") (name "unconnected-(U1A-PB1{slash}SYNC{slash}ADC1{slash}AC1-Pad6)") (class "Default")
      (node (ref "U1") (pin "6") (pinfunction "PB1/SYNC/ADC1/AC1_6") (pintype "bidirectional"))
    )
  )
)
